# ethernet_top_board.net
KiCad netlist of a schematic drawn in EAGLE
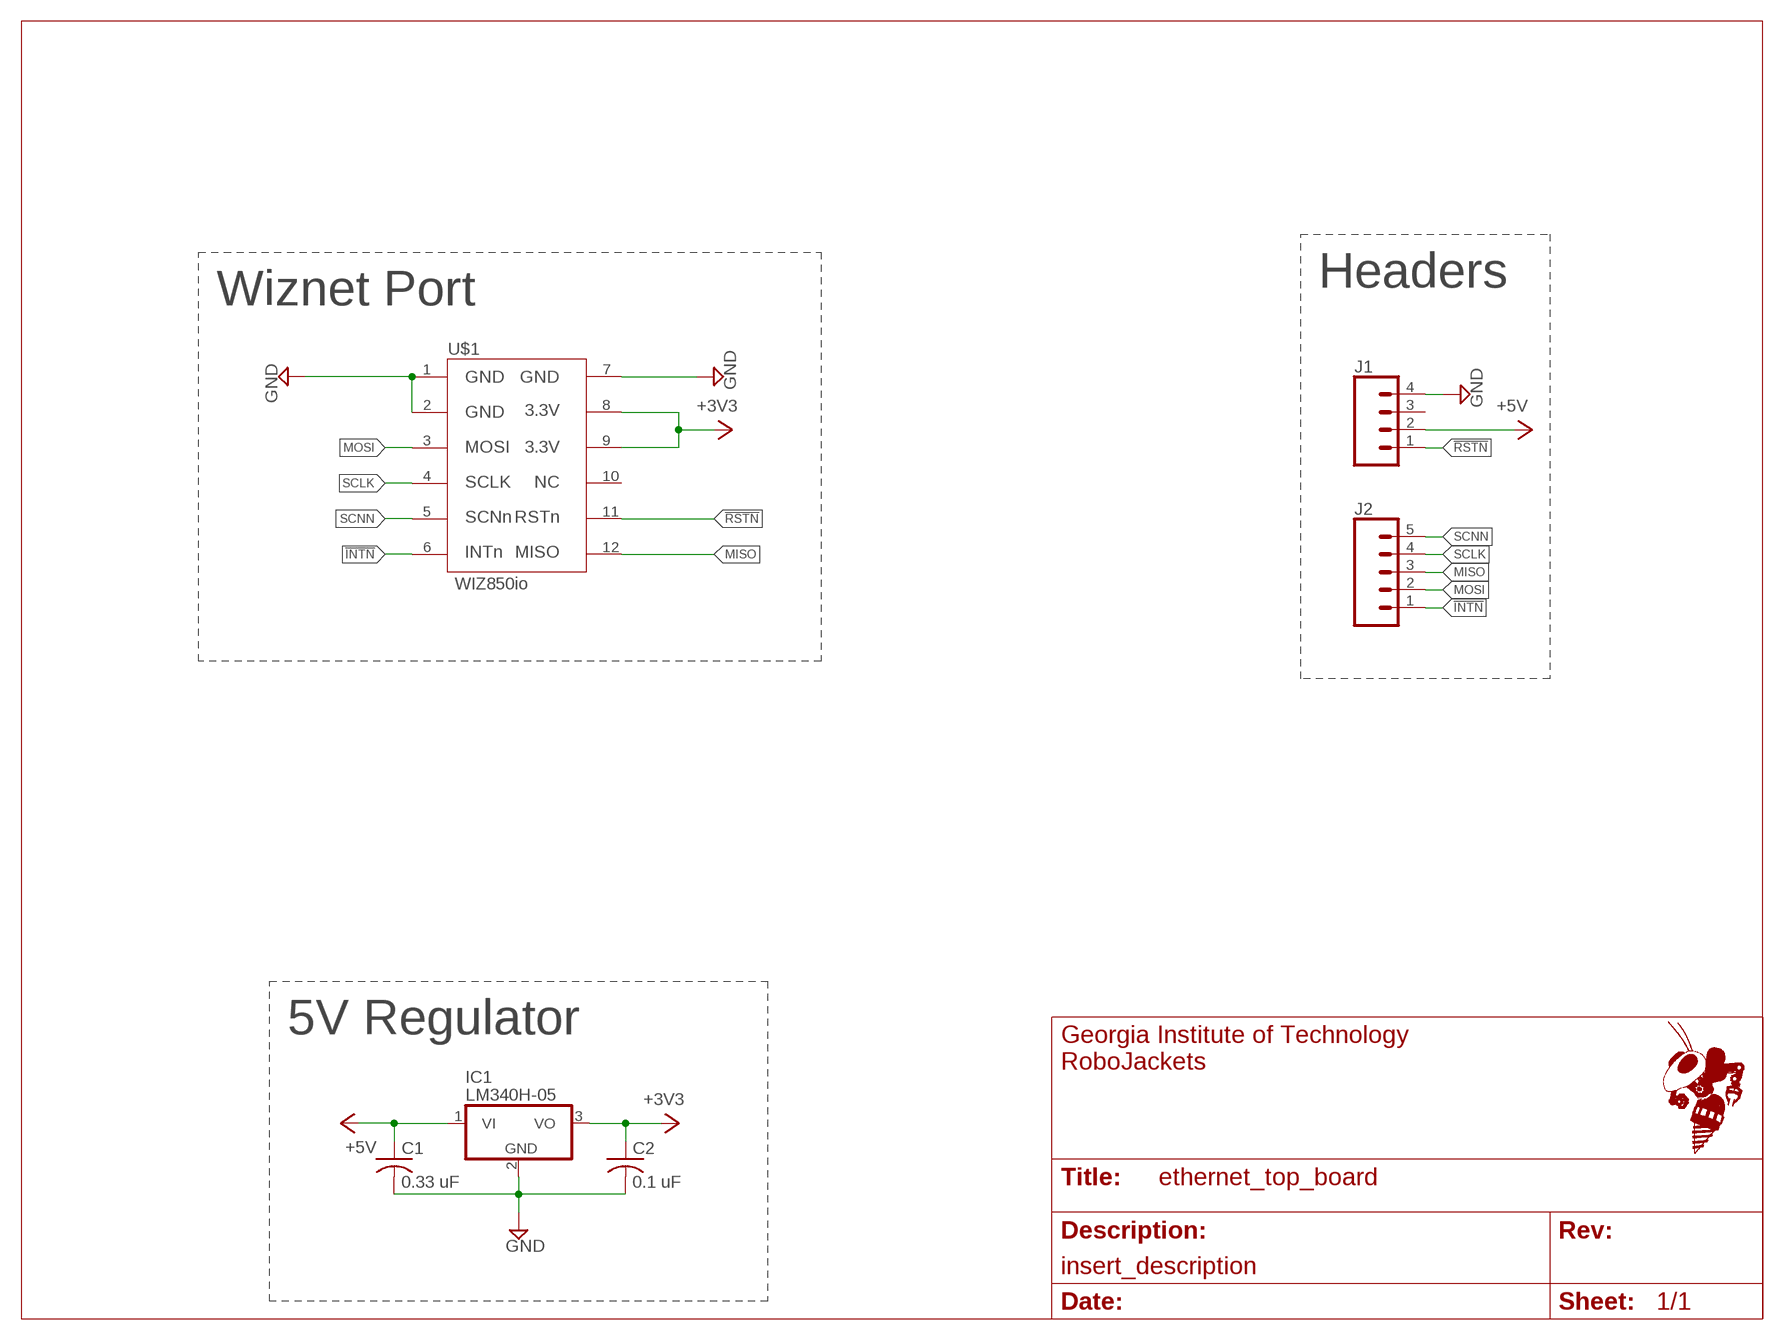
[diagram p0: schematic, sheet 1]

(export (version "E")
  (design (tool "Eeschema 10.0.6"))
  (components
    (comp (ref "C1")
      (value "0.33 uF")
      (footprint "eagle-import:C0603")
      (libsource (lib "eagle-import") (part "C-USC0603"))
    )
    (comp (ref "C2")
      (value "0.1 uF")
      (footprint "eagle-import:C0603")
      (libsource (lib "eagle-import") (part "C-USC0603"))
    )
    (comp (ref "IC1")
      (value "LM340H-05")
      (footprint "eagle-import:TO220H")
      (libsource (lib "eagle-import") (part "LM340?-H05"))
    )
    (comp (ref "J1")
      (value "CONN_04")
      (footprint "eagle-import:1X04")
      (libsource (lib "eagle-import") (part "CONN_04"))
    )
    (comp (ref "J2")
      (value "CONN_05")
      (footprint "eagle-import:1X05")
      (libsource (lib "eagle-import") (part "CONN_05"))
    )
    (comp (ref "U$1")
      (value "WIZ850IO")
      (footprint "eagle-import:WIZ850IO")
      (libsource (lib "eagle-import") (part "WIZ850IO"))
    )
  )
  (nets
    (net (code "1") (name "+3V3") (class "Default")
      (node (ref "C2") (pin "1") (pinfunction "1_1") (pintype "passive"))
      (node (ref "IC1") (pin "3") (pinfunction "VO_3") (pintype "passive"))
      (node (ref "U$1") (pin "8") (pinfunction "8_8") (pintype "bidirectional"))
      (node (ref "U$1") (pin "9") (pinfunction "9_9") (pintype "bidirectional"))
    )
    (net (code "2") (name "+5V") (class "Default")
      (node (ref "C1") (pin "1") (pinfunction "1_1") (pintype "passive"))
      (node (ref "IC1") (pin "1") (pinfunction "VI_1") (pintype "input"))
      (node (ref "J1") (pin "2") (pinfunction "2_2") (pintype "passive"))
    )
    (net (code "3") (name "/~{INTN}") (class "Default")
      (node (ref "J2") (pin "1") (pinfunction "1_1") (pintype "passive"))
      (node (ref "U$1") (pin "6") (pinfunction "6_6") (pintype "bidirectional"))
    )
    (net (code "4") (name "/~{RSTN}") (class "Default")
      (node (ref "J1") (pin "1") (pinfunction "1_1") (pintype "passive"))
      (node (ref "U$1") (pin "11") (pinfunction "11_11") (pintype "bidirectional"))
    )
    (net (code "5") (name "GND") (class "Default")
      (node (ref "C1") (pin "2") (pinfunction "2_2") (pintype "passive"))
      (node (ref "C2") (pin "2") (pinfunction "2_2") (pintype "passive"))
      (node (ref "IC1") (pin "2") (pinfunction "GND_2") (pintype "passive"))
      (node (ref "J1") (pin "4") (pinfunction "4_4") (pintype "passive"))
      (node (ref "U$1") (pin "1") (pinfunction "1_1") (pintype "bidirectional"))
      (node (ref "U$1") (pin "2") (pinfunction "2_2") (pintype "bidirectional"))
      (node (ref "U$1") (pin "7") (pinfunction "7_7") (pintype "bidirectional"))
    )
    (net (code "6") (name "MISO") (class "Default")
      (node (ref "J2") (pin "3") (pinfunction "3_3") (pintype "passive"))
      (node (ref "U$1") (pin "12") (pinfunction "12_12") (pintype "bidirectional"))
    )
    (net (code "7") (name "MOSI") (class "Default")
      (node (ref "J2") (pin "2") (pinfunction "2_2") (pintype "passive"))
      (node (ref "U$1") (pin "3") (pinfunction "3_3") (pintype "bidirectional"))
    )
    (net (code "8") (name "SCLK") (class "Default")
      (node (ref "J2") (pin "4") (pinfunction "4_4") (pintype "passive"))
      (node (ref "U$1") (pin "4") (pinfunction "4_4") (pintype "bidirectional"))
    )
    (net (code "9") (name "SCNN") (class "Default")
      (node (ref "J2") (pin "5") (pinfunction "5_5") (pintype "passive"))
      (node (ref "U$1") (pin "5") (pinfunction "5_5") (pintype "bidirectional"))
    )
    (net (code "10") (name "unconnected-(J1-Pad3)") (class "Default")
      (node (ref "J1") (pin "3") (pinfunction "3_3") (pintype "passive"))
    )
    (net (code "11") (name "unconnected-(U$1-Pad10)") (class "Default")
      (node (ref "U$1") (pin "10") (pinfunction "10_10") (pintype "bidirectional"))
    )
  )
)
